# OLED-Sensor_Long_Link.net
KiCad netlist of a schematic drawn in EAGLE
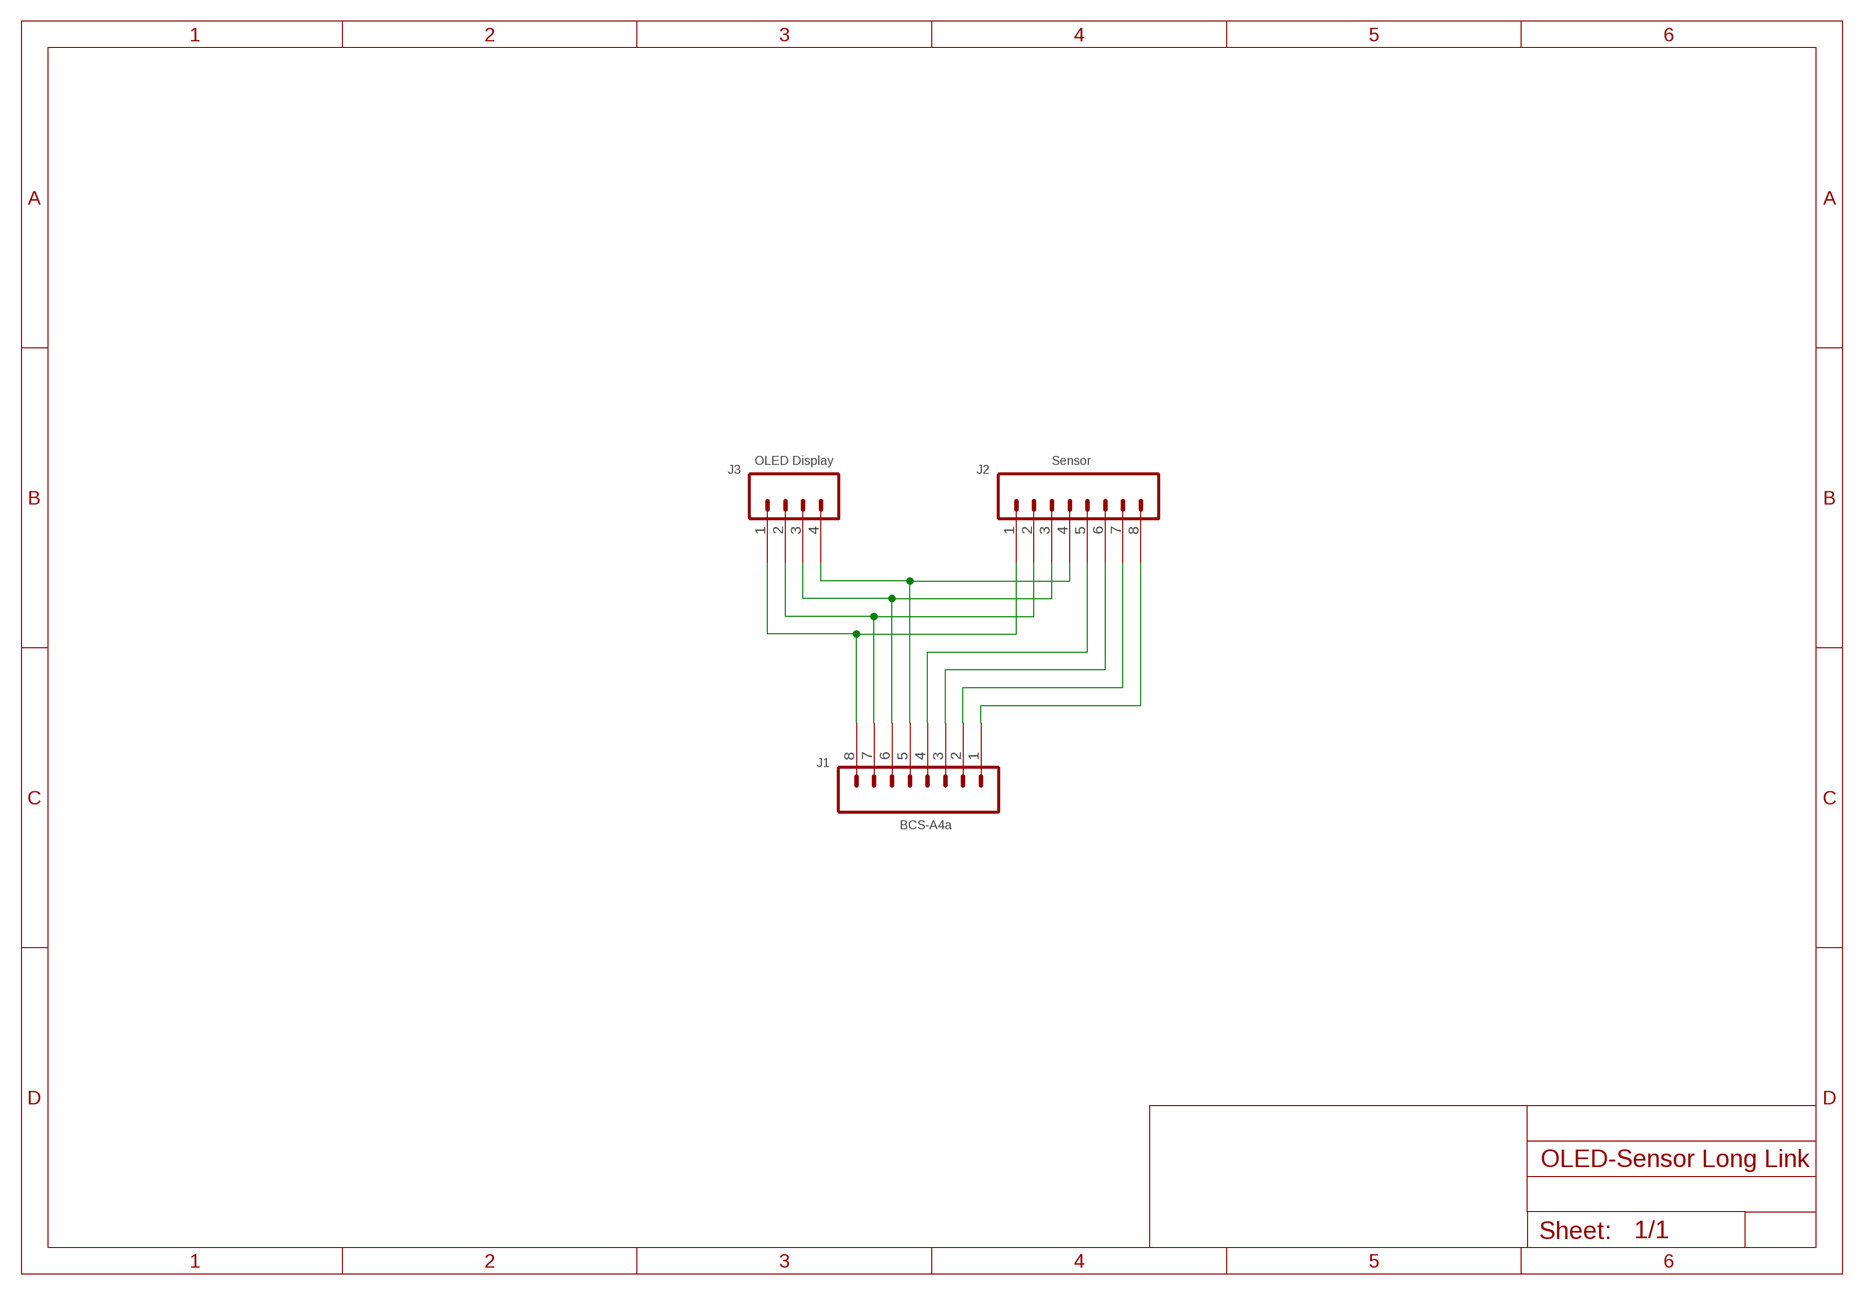
[diagram p0: schematic, sheet 1]

(export (version "E")
  (design (tool "Eeschema 10.0.6"))
  (components
    (comp (ref "J1")
      (value "BCS-A4a")
      (footprint "eagle-import:CONN_08-GENERIC")
      (libsource (lib "eagle-import") (part "HEADER-1X8-GENERIC"))
    )
    (comp (ref "J2")
      (value "Sensor")
      (footprint "eagle-import:CONN_08-GENERIC")
      (libsource (lib "eagle-import") (part "HEADER-1X8-GENERIC"))
    )
    (comp (ref "J3")
      (value "OLED Display")
      (footprint "eagle-import:CONN_04-GENERIC")
      (libsource (lib "eagle-import") (part "HEADER-1X4-GENERIC"))
    )
  )
  (nets
    (net (code "1") (name "Net-(J1-Pad1)") (class "Default")
      (node (ref "J1") (pin "1") (pinfunction "1_1") (pintype "passive"))
      (node (ref "J2") (pin "8") (pinfunction "8_8") (pintype "passive"))
    )
    (net (code "2") (name "Net-(J1-Pad2)") (class "Default")
      (node (ref "J1") (pin "2") (pinfunction "2_2") (pintype "passive"))
      (node (ref "J2") (pin "7") (pinfunction "7_7") (pintype "passive"))
    )
    (net (code "3") (name "Net-(J1-Pad3)") (class "Default")
      (node (ref "J1") (pin "3") (pinfunction "3_3") (pintype "passive"))
      (node (ref "J2") (pin "6") (pinfunction "6_6") (pintype "passive"))
    )
    (net (code "4") (name "Net-(J1-Pad4)") (class "Default")
      (node (ref "J1") (pin "4") (pinfunction "4_4") (pintype "passive"))
      (node (ref "J2") (pin "5") (pinfunction "5_5") (pintype "passive"))
    )
    (net (code "5") (name "Net-(J1-Pad5)") (class "Default")
      (node (ref "J1") (pin "5") (pinfunction "5_5") (pintype "passive"))
      (node (ref "J2") (pin "4") (pinfunction "4_4") (pintype "passive"))
      (node (ref "J3") (pin "4") (pinfunction "4_4") (pintype "passive"))
    )
    (net (code "6") (name "Net-(J1-Pad6)") (class "Default")
      (node (ref "J1") (pin "6") (pinfunction "6_6") (pintype "passive"))
      (node (ref "J2") (pin "3") (pinfunction "3_3") (pintype "passive"))
      (node (ref "J3") (pin "3") (pinfunction "3_3") (pintype "passive"))
    )
    (net (code "7") (name "Net-(J1-Pad7)") (class "Default")
      (node (ref "J1") (pin "7") (pinfunction "7_7") (pintype "passive"))
      (node (ref "J2") (pin "2") (pinfunction "2_2") (pintype "passive"))
      (node (ref "J3") (pin "2") (pinfunction "2_2") (pintype "passive"))
    )
    (net (code "8") (name "Net-(J1-Pad8)") (class "Default")
      (node (ref "J1") (pin "8") (pinfunction "8_8") (pintype "passive"))
      (node (ref "J2") (pin "1") (pinfunction "1_1") (pintype "passive"))
      (node (ref "J3") (pin "1") (pinfunction "1_1") (pintype "passive"))
    )
  )
)
